# 555_Clocked_LED.net
KiCad netlist of a schematic drawn in Altium Designer
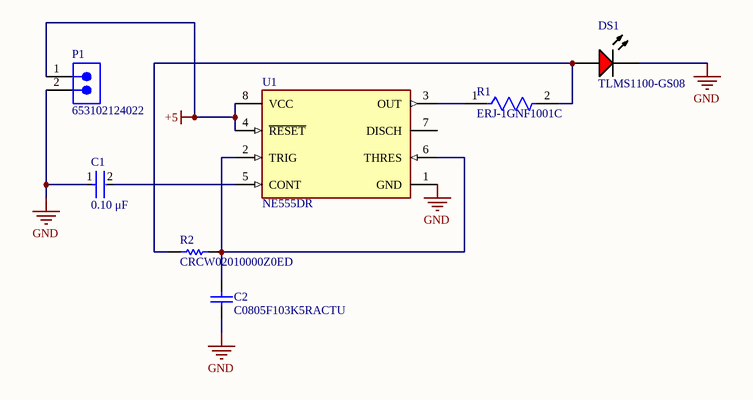
[diagram p0: 555 Clocked LED.SchDoc]

(export (version "E")
  (design (tool "Eeschema 10.0.6"))
  (components
    (comp (ref "C1")
      (value "0.10 μF")
      (footprint "FP-C1206C-EB-IPC_A")
      (description "CAP CER 0.1UF 200V 10% X7R 1206")
      (fields (field (name "TOLERANCE") "0.1") (field (name "MANUFACTURER PART NUMBER") "C1206C104K2RACTU"))
      (libsource (lib "Altium Content Vault") (part "b4654b650e69147ec39a6b967a45e02"))
    )
    (comp (ref "C2")
      (value "C0805F103K5RACTU")
      (footprint "CAPC2013X100X50LL20T25")
      (fields (field (name "MANUFACTURER") "Kemet"))
      (libsource (lib "Altium Content Vault") (part "CAP"))
    )
    (comp (ref "DS1")
      (value "TLMS1100-GS08")
      (footprint "VISH-TLMX1100_V")
      (description "LED, RED, 2.1 V, -40 to 100 degC, 2-Pin SMD (0603), RoHS, Tape and Reel")
      (fields (field (name "TOLERANCE") "5%"))
      (libsource (lib "Altium Content Vault") (part "LED-RED-AK-2"))
    )
    (comp (ref "P1")
      (value "653102124022")
      (footprint "653102124022")
      (libsource (lib "Altium Content Vault") (part "Header_Male_1R_02P"))
    )
    (comp (ref "R1")
      (value "ERJ-1GNF1001C")
      (footprint "FP-ERJ1GN-MFG")
      (description "RES SMD 1K OHM 1% 1/20W 0201")
      (fields (field (name "TOLERANCE") "1%"))
      (libsource (lib "Altium Content Vault") (part "1029c3af85768c4190bb7ad29bc67b5"))
    )
    (comp (ref "R2")
      (value "CRCW02010000Z0ED")
      (footprint "RESC0603X28X15ML5T05")
      (description "Chip Resistor, 0 Ohm, Jumper, 0.05 W, -55 to 155 degC, 0201 (0603 Metric), RoHS, Tape and Reel")
      (fields (field (name "TOLERANCE") "5%"))
      (libsource (lib "Altium Content Vault") (part "RES-2"))
    )
    (comp (ref "U1")
      (value "NE555DR")
      (footprint "FP-D0008A-IPC_C")
      (description "IC OSC SGL TIMER 100KHZ 8-SOIC")
      (libsource (lib "Altium Content Vault") (part "a29bba90211dec1890110b94dad7d53"))
    )
  )
  (nets
    (net (code "1") (name "+5") (class "Default")
      (node (ref "P1") (pin "1") (pinfunction "1_1") (pintype "passive"))
      (node (ref "U1") (pin "4") (pinfunction "~{RESET}_4") (pintype "input"))
      (node (ref "U1") (pin "8") (pinfunction "VCC_8") (pintype "power_in"))
    )
    (net (code "2") (name "GND") (class "Default")
      (node (ref "C1") (pin "1") (pinfunction "1_1") (pintype "passive"))
      (node (ref "C2") (pin "1") (pinfunction "1_1") (pintype "passive"))
      (node (ref "DS1") (pin "2") (pinfunction "K_2") (pintype "passive"))
      (node (ref "P1") (pin "2") (pinfunction "2_2") (pintype "passive"))
      (node (ref "U1") (pin "1") (pinfunction "GND_1") (pintype "power_in"))
    )
    (net (code "3") (name "Net-(DS1-A)") (class "Default")
      (node (ref "DS1") (pin "1") (pinfunction "A_1") (pintype "passive"))
      (node (ref "R1") (pin "2") (pinfunction "2_2") (pintype "passive"))
      (node (ref "R2") (pin "1") (pinfunction "1_1") (pintype "passive"))
    )
    (net (code "4") (name "Net-(U1-CONT)") (class "Default")
      (node (ref "C1") (pin "2") (pinfunction "2_2") (pintype "passive"))
      (node (ref "U1") (pin "5") (pinfunction "CONT_5") (pintype "input"))
    )
    (net (code "5") (name "Net-(U1-OUT)") (class "Default")
      (node (ref "R1") (pin "1") (pinfunction "1_1") (pintype "passive"))
      (node (ref "U1") (pin "3") (pinfunction "OUT_3") (pintype "output"))
    )
    (net (code "6") (name "Net-(U1-THRES)") (class "Default")
      (node (ref "C2") (pin "2") (pinfunction "2_2") (pintype "passive"))
      (node (ref "R2") (pin "2") (pinfunction "2_2") (pintype "passive"))
      (node (ref "U1") (pin "2") (pinfunction "TRIG_2") (pintype "input"))
      (node (ref "U1") (pin "6") (pinfunction "THRES_6") (pintype "input"))
    )
    (net (code "7") (name "unconnected-(U1-DISCH-Pad7)") (class "Default")
      (node (ref "U1") (pin "7") (pinfunction "DISCH_7") (pintype "open_collector"))
    )
  )
)
